# DDR3_1.net
KiCad netlist of a schematic drawn in Altium Designer
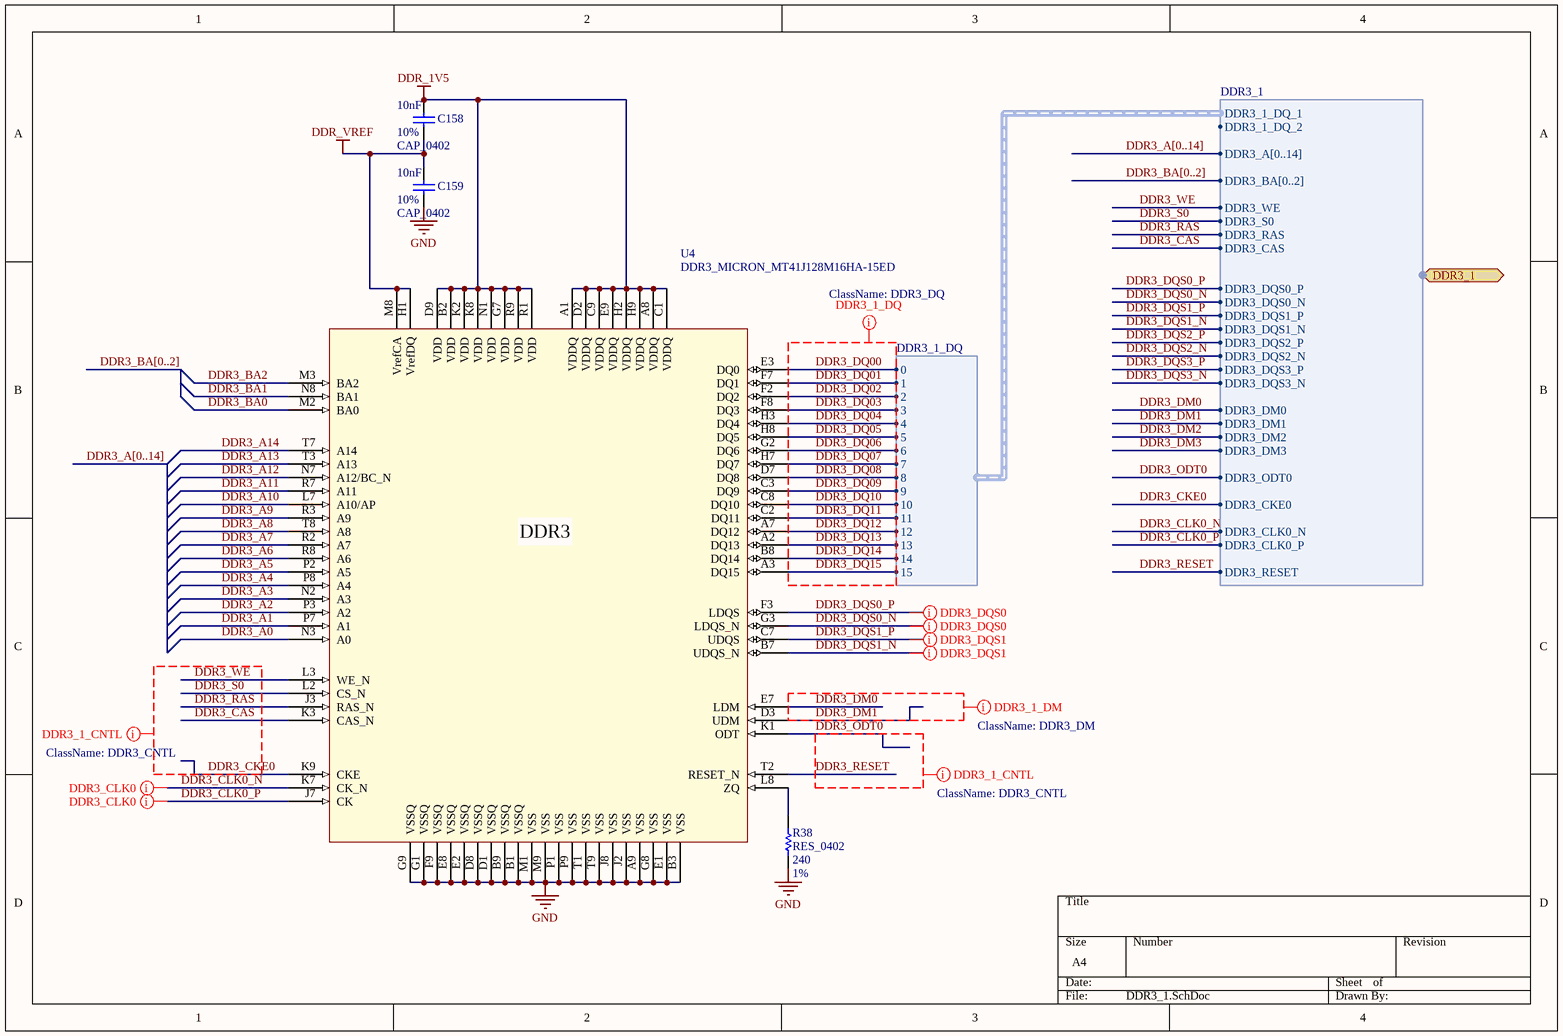
[diagram p0: DDR3_1.SchDoc]

(export (version "E")
  (design (tool "Eeschema 10.0.6"))
  (components
    (comp (ref "C158")
      (value "CAP_0402")
      (footprint "CAPC0402(1005)60_N:CAPC0402(1005)60_N")
      (description "10000pF, ceramic, 10% 6.3V X5R, 0402")
      (fields
        (field (name "ALTIUM_VALUE") "10nF")
        (field (name "TOLERANCE") "10%")
        (field (name "PART NUMBER") "GRM155R60J103KA01D")
        (field (name "MANUFACTURER") "Murata Electronics North America")
      )
      (libsource (lib "COMRAD_Database") (part "CAP_0402"))
    )
    (comp (ref "C159")
      (value "CAP_0402")
      (footprint "CAPC0402(1005)60_N:CAPC0402(1005)60_N")
      (description "10000pF, ceramic, 10% 6.3V X5R, 0402")
      (fields
        (field (name "ALTIUM_VALUE") "10nF")
        (field (name "TOLERANCE") "10%")
        (field (name "PART NUMBER") "GRM155R60J103KA01D")
        (field (name "MANUFACTURER") "Murata Electronics North America")
      )
      (libsource (lib "COMRAD_Database") (part "CAP_0402"))
    )
    (comp (ref "R38")
      (value "RES_0402")
      (footprint "RESC0402(1005)_N:RESC0402(1005)_N")
      (description "240 ohm, 1% 1/16W, 0402")
      (fields
        (field (name "ALTIUM_VALUE") "240")
        (field (name "TOLERANCE") "1%")
        (field (name "PART NUMBER") "CRCW0402240RFKED")
        (field (name "MANUFACTURER") "Vishay/Dale")
      )
      (libsource (lib "COMRAD_Database") (part "RES_0402"))
    )
    (comp (ref "U4")
      (value "DDR3_MICRON_MT41J128M16HA-15ED")
      (footprint "DDR3_MICRON_MT41J128M16HA-15ED_FBGA96")
      (description "MT41J128M16HA-15E:D, DDR3 SDRAM 4Gb x4, x8, x16, FBGA96")
      (fields (field (name "PART NUMBER") "MT41J128M16HA-15E:D TR") (field (name "MANUFACTURER") "MICRON"))
      (libsource (lib "COMRAD_Database") (part "DDR3_MICRON_MT41J128M16HA-15ED"))
    )
  )
  (nets
    (net (code "4") (name "/DDR3_A0") (class "Default")
      (node (ref "U4") (pin "N3") (pinfunction "A0_N3") (pintype "input"))
    )
    (net (code "5") (name "/DDR3_A1") (class "Default")
      (node (ref "U4") (pin "P7") (pinfunction "A1_P7") (pintype "input"))
    )
    (net (code "6") (name "/DDR3_A2") (class "Default")
      (node (ref "U4") (pin "P3") (pinfunction "A2_P3") (pintype "input"))
    )
    (net (code "7") (name "/DDR3_A3") (class "Default")
      (node (ref "U4") (pin "N2") (pinfunction "A3_N2") (pintype "input"))
    )
    (net (code "8") (name "/DDR3_A4") (class "Default")
      (node (ref "U4") (pin "P8") (pinfunction "A4_P8") (pintype "input"))
    )
    (net (code "9") (name "/DDR3_A5") (class "Default")
      (node (ref "U4") (pin "P2") (pinfunction "A5_P2") (pintype "input"))
    )
    (net (code "10") (name "/DDR3_A6") (class "Default")
      (node (ref "U4") (pin "R8") (pinfunction "A6_R8") (pintype "input"))
    )
    (net (code "11") (name "/DDR3_A7") (class "Default")
      (node (ref "U4") (pin "R2") (pinfunction "A7_R2") (pintype "input"))
    )
    (net (code "12") (name "/DDR3_A8") (class "Default")
      (node (ref "U4") (pin "T8") (pinfunction "A8_T8") (pintype "input"))
    )
    (net (code "13") (name "/DDR3_A9") (class "Default")
      (node (ref "U4") (pin "R3") (pinfunction "A9_R3") (pintype "input"))
    )
    (net (code "14") (name "/DDR3_A10") (class "Default")
      (node (ref "U4") (pin "L7") (pinfunction "A10/AP_L7") (pintype "input"))
    )
    (net (code "15") (name "/DDR3_A11") (class "Default")
      (node (ref "U4") (pin "R7") (pinfunction "A11_R7") (pintype "input"))
    )
    (net (code "16") (name "/DDR3_A12") (class "Default")
      (node (ref "U4") (pin "N7") (pinfunction "A12/BC_N_N7") (pintype "input"))
    )
    (net (code "17") (name "/DDR3_A13") (class "Default")
      (node (ref "U4") (pin "T3") (pinfunction "A13_T3") (pintype "input"))
    )
    (net (code "18") (name "/DDR3_A14") (class "Default")
      (node (ref "U4") (pin "T7") (pinfunction "A14_T7") (pintype "input"))
    )
    (net (code "20") (name "/DDR3_BA0") (class "Default")
      (node (ref "U4") (pin "M2") (pinfunction "BA0_M2") (pintype "input"))
    )
    (net (code "21") (name "/DDR3_BA1") (class "Default")
      (node (ref "U4") (pin "N8") (pinfunction "BA1_N8") (pintype "input"))
    )
    (net (code "22") (name "/DDR3_BA2") (class "Default")
      (node (ref "U4") (pin "M3") (pinfunction "BA2_M3") (pintype "input"))
    )
    (net (code "24") (name "/DDR3_CAS") (class "Default")
      (node (ref "U4") (pin "K3") (pinfunction "CAS_N_K3") (pintype "input"))
    )
    (net (code "25") (name "/DDR3_CKE0") (class "Default")
      (node (ref "U4") (pin "K9") (pinfunction "CKE_K9") (pintype "input"))
    )
    (net (code "26") (name "/DDR3_CLK0_N") (class "Default")
      (node (ref "U4") (pin "K7") (pinfunction "CK_N_K7") (pintype "input"))
    )
    (net (code "27") (name "/DDR3_CLK0_P") (class "Default")
      (node (ref "U4") (pin "J7") (pinfunction "CK_J7") (pintype "input"))
    )
    (net (code "28") (name "/DDR3_DM0") (class "Default")
      (node (ref "U4") (pin "E7") (pinfunction "LDM_E7") (pintype "input"))
    )
    (net (code "29") (name "/DDR3_DM1") (class "Default")
      (node (ref "U4") (pin "D3") (pinfunction "UDM_D3") (pintype "input"))
    )
    (net (code "32") (name "/DDR3_DQ00") (class "Default")
      (node (ref "U4") (pin "E3") (pinfunction "DQ0_E3") (pintype "bidirectional"))
    )
    (net (code "33") (name "/DDR3_DQ01") (class "Default")
      (node (ref "U4") (pin "F7") (pinfunction "DQ1_F7") (pintype "bidirectional"))
    )
    (net (code "34") (name "/DDR3_DQ02") (class "Default")
      (node (ref "U4") (pin "F2") (pinfunction "DQ2_F2") (pintype "bidirectional"))
    )
    (net (code "35") (name "/DDR3_DQ03") (class "Default")
      (node (ref "U4") (pin "F8") (pinfunction "DQ3_F8") (pintype "bidirectional"))
    )
    (net (code "36") (name "/DDR3_DQ04") (class "Default")
      (node (ref "U4") (pin "H3") (pinfunction "DQ4_H3") (pintype "bidirectional"))
    )
    (net (code "37") (name "/DDR3_DQ05") (class "Default")
      (node (ref "U4") (pin "H8") (pinfunction "DQ5_H8") (pintype "bidirectional"))
    )
    (net (code "38") (name "/DDR3_DQ06") (class "Default")
      (node (ref "U4") (pin "G2") (pinfunction "DQ6_G2") (pintype "bidirectional"))
    )
    (net (code "39") (name "/DDR3_DQ07") (class "Default")
      (node (ref "U4") (pin "H7") (pinfunction "DQ7_H7") (pintype "bidirectional"))
    )
    (net (code "40") (name "/DDR3_DQ08") (class "Default")
      (node (ref "U4") (pin "D7") (pinfunction "DQ8_D7") (pintype "bidirectional"))
    )
    (net (code "41") (name "/DDR3_DQ09") (class "Default")
      (node (ref "U4") (pin "C3") (pinfunction "DQ9_C3") (pintype "bidirectional"))
    )
    (net (code "42") (name "/DDR3_DQ10") (class "Default")
      (node (ref "U4") (pin "C8") (pinfunction "DQ10_C8") (pintype "bidirectional"))
    )
    (net (code "43") (name "/DDR3_DQ11") (class "Default")
      (node (ref "U4") (pin "C2") (pinfunction "DQ11_C2") (pintype "bidirectional"))
    )
    (net (code "44") (name "/DDR3_DQ12") (class "Default")
      (node (ref "U4") (pin "A7") (pinfunction "DQ12_A7") (pintype "bidirectional"))
    )
    (net (code "45") (name "/DDR3_DQ13") (class "Default")
      (node (ref "U4") (pin "A2") (pinfunction "DQ13_A2") (pintype "bidirectional"))
    )
    (net (code "46") (name "/DDR3_DQ14") (class "Default")
      (node (ref "U4") (pin "B8") (pinfunction "DQ14_B8") (pintype "bidirectional"))
    )
    (net (code "47") (name "/DDR3_DQ15") (class "Default")
      (node (ref "U4") (pin "A3") (pinfunction "DQ15_A3") (pintype "bidirectional"))
    )
    (net (code "48") (name "/DDR3_DQS0_N") (class "Default")
      (node (ref "U4") (pin "G3") (pinfunction "LDQS_N_G3") (pintype "bidirectional"))
    )
    (net (code "49") (name "/DDR3_DQS0_P") (class "Default")
      (node (ref "U4") (pin "F3") (pinfunction "LDQS_F3") (pintype "bidirectional"))
    )
    (net (code "50") (name "/DDR3_DQS1_N") (class "Default")
      (node (ref "U4") (pin "B7") (pinfunction "UDQS_N_B7") (pintype "bidirectional"))
    )
    (net (code "51") (name "/DDR3_DQS1_P") (class "Default")
      (node (ref "U4") (pin "C7") (pinfunction "UDQS_C7") (pintype "bidirectional"))
    )
    (net (code "56") (name "/DDR3_ODT0") (class "Default")
      (node (ref "U4") (pin "K1") (pinfunction "ODT_K1") (pintype "input"))
    )
    (net (code "57") (name "/DDR3_RAS") (class "Default")
      (node (ref "U4") (pin "J3") (pinfunction "RAS_N_J3") (pintype "input"))
    )
    (net (code "58") (name "/DDR3_RESET") (class "Default")
      (node (ref "U4") (pin "T2") (pinfunction "RESET_N_T2") (pintype "input"))
    )
    (net (code "59") (name "/DDR3_S0") (class "Default")
      (node (ref "U4") (pin "L2") (pinfunction "CS_N_L2") (pintype "input"))
    )
    (net (code "60") (name "/DDR3_WE") (class "Default")
      (node (ref "U4") (pin "L3") (pinfunction "WE_N_L3") (pintype "input"))
    )
    (net (code "63") (name "DDR_1V5") (class "Default")
      (node (ref "C158") (pin "2") (pinfunction "2_2") (pintype "passive"))
      (node (ref "U4") (pin "A1") (pinfunction "VDDQ_A1") (pintype "power_in"))
      (node (ref "U4") (pin "A8") (pinfunction "VDDQ_A8") (pintype "power_in"))
      (node (ref "U4") (pin "B2") (pinfunction "VDD_B2") (pintype "power_in"))
      (node (ref "U4") (pin "C1") (pinfunction "VDDQ_C1") (pintype "power_in"))
      (node (ref "U4") (pin "C9") (pinfunction "VDDQ_C9") (pintype "power_in"))
      (node (ref "U4") (pin "D2") (pinfunction "VDDQ_D2") (pintype "power_in"))
      (node (ref "U4") (pin "D9") (pinfunction "VDD_D9") (pintype "power_in"))
      (node (ref "U4") (pin "E9") (pinfunction "VDDQ_E9") (pintype "power_in"))
      (node (ref "U4") (pin "G7") (pinfunction "VDD_G7") (pintype "power_in"))
      (node (ref "U4") (pin "H2") (pinfunction "VDDQ_H2") (pintype "power_in"))
      (node (ref "U4") (pin "H9") (pinfunction "VDDQ_H9") (pintype "power_in"))
      (node (ref "U4") (pin "K2") (pinfunction "VDD_K2") (pintype "power_in"))
      (node (ref "U4") (pin "K8") (pinfunction "VDD_K8") (pintype "power_in"))
      (node (ref "U4") (pin "N1") (pinfunction "VDD_N1") (pintype "power_in"))
      (node (ref "U4") (pin "R1") (pinfunction "VDD_R1") (pintype "power_in"))
      (node (ref "U4") (pin "R9") (pinfunction "VDD_R9") (pintype "power_in"))
    )
    (net (code "64") (name "DDR_VREF") (class "Default")
      (node (ref "C158") (pin "1") (pinfunction "1_1") (pintype "passive"))
      (node (ref "C159") (pin "2") (pinfunction "2_2") (pintype "passive"))
      (node (ref "U4") (pin "H1") (pinfunction "VrefDQ_H1") (pintype "power_in"))
      (node (ref "U4") (pin "M8") (pinfunction "VrefCA_M8") (pintype "power_in"))
    )
    (net (code "65") (name "GND") (class "Default")
      (node (ref "C159") (pin "1") (pinfunction "1_1") (pintype "passive"))
      (node (ref "R38") (pin "1") (pinfunction "1_1") (pintype "passive"))
      (node (ref "U4") (pin "A9") (pinfunction "VSS_A9") (pintype "power_in"))
      (node (ref "U4") (pin "B1") (pinfunction "VSSQ_B1") (pintype "power_in"))
      (node (ref "U4") (pin "B3") (pinfunction "VSS_B3") (pintype "power_in"))
      (node (ref "U4") (pin "B9") (pinfunction "VSSQ_B9") (pintype "power_in"))
      (node (ref "U4") (pin "D1") (pinfunction "VSSQ_D1") (pintype "power_in"))
      (node (ref "U4") (pin "D8") (pinfunction "VSSQ_D8") (pintype "power_in"))
      (node (ref "U4") (pin "E1") (pinfunction "VSS_E1") (pintype "power_in"))
      (node (ref "U4") (pin "E2") (pinfunction "VSSQ_E2") (pintype "power_in"))
      (node (ref "U4") (pin "E8") (pinfunction "VSSQ_E8") (pintype "power_in"))
      (node (ref "U4") (pin "F9") (pinfunction "VSSQ_F9") (pintype "power_in"))
      (node (ref "U4") (pin "G1") (pinfunction "VSSQ_G1") (pintype "power_in"))
      (node (ref "U4") (pin "G8") (pinfunction "VSS_G8") (pintype "power_in"))
      (node (ref "U4") (pin "G9") (pinfunction "VSSQ_G9") (pintype "power_in"))
      (node (ref "U4") (pin "J2") (pinfunction "VSS_J2") (pintype "power_in"))
      (node (ref "U4") (pin "J8") (pinfunction "VSS_J8") (pintype "power_in"))
      (node (ref "U4") (pin "M1") (pinfunction "VSS_M1") (pintype "power_in"))
      (node (ref "U4") (pin "M9") (pinfunction "VSS_M9") (pintype "power_in"))
      (node (ref "U4") (pin "P1") (pinfunction "VSS_P1") (pintype "power_in"))
      (node (ref "U4") (pin "P9") (pinfunction "VSS_P9") (pintype "power_in"))
      (node (ref "U4") (pin "T1") (pinfunction "VSS_T1") (pintype "power_in"))
      (node (ref "U4") (pin "T9") (pinfunction "VSS_T9") (pintype "power_in"))
    )
    (net (code "66") (name "Net-(U4-ZQ)") (class "Default")
      (node (ref "R38") (pin "2") (pinfunction "2_2") (pintype "passive"))
      (node (ref "U4") (pin "L8") (pinfunction "ZQ_L8") (pintype "input"))
    )
  )
)
